# NeoCoreShield2.net
KiCad netlist of a schematic drawn in EAGLE
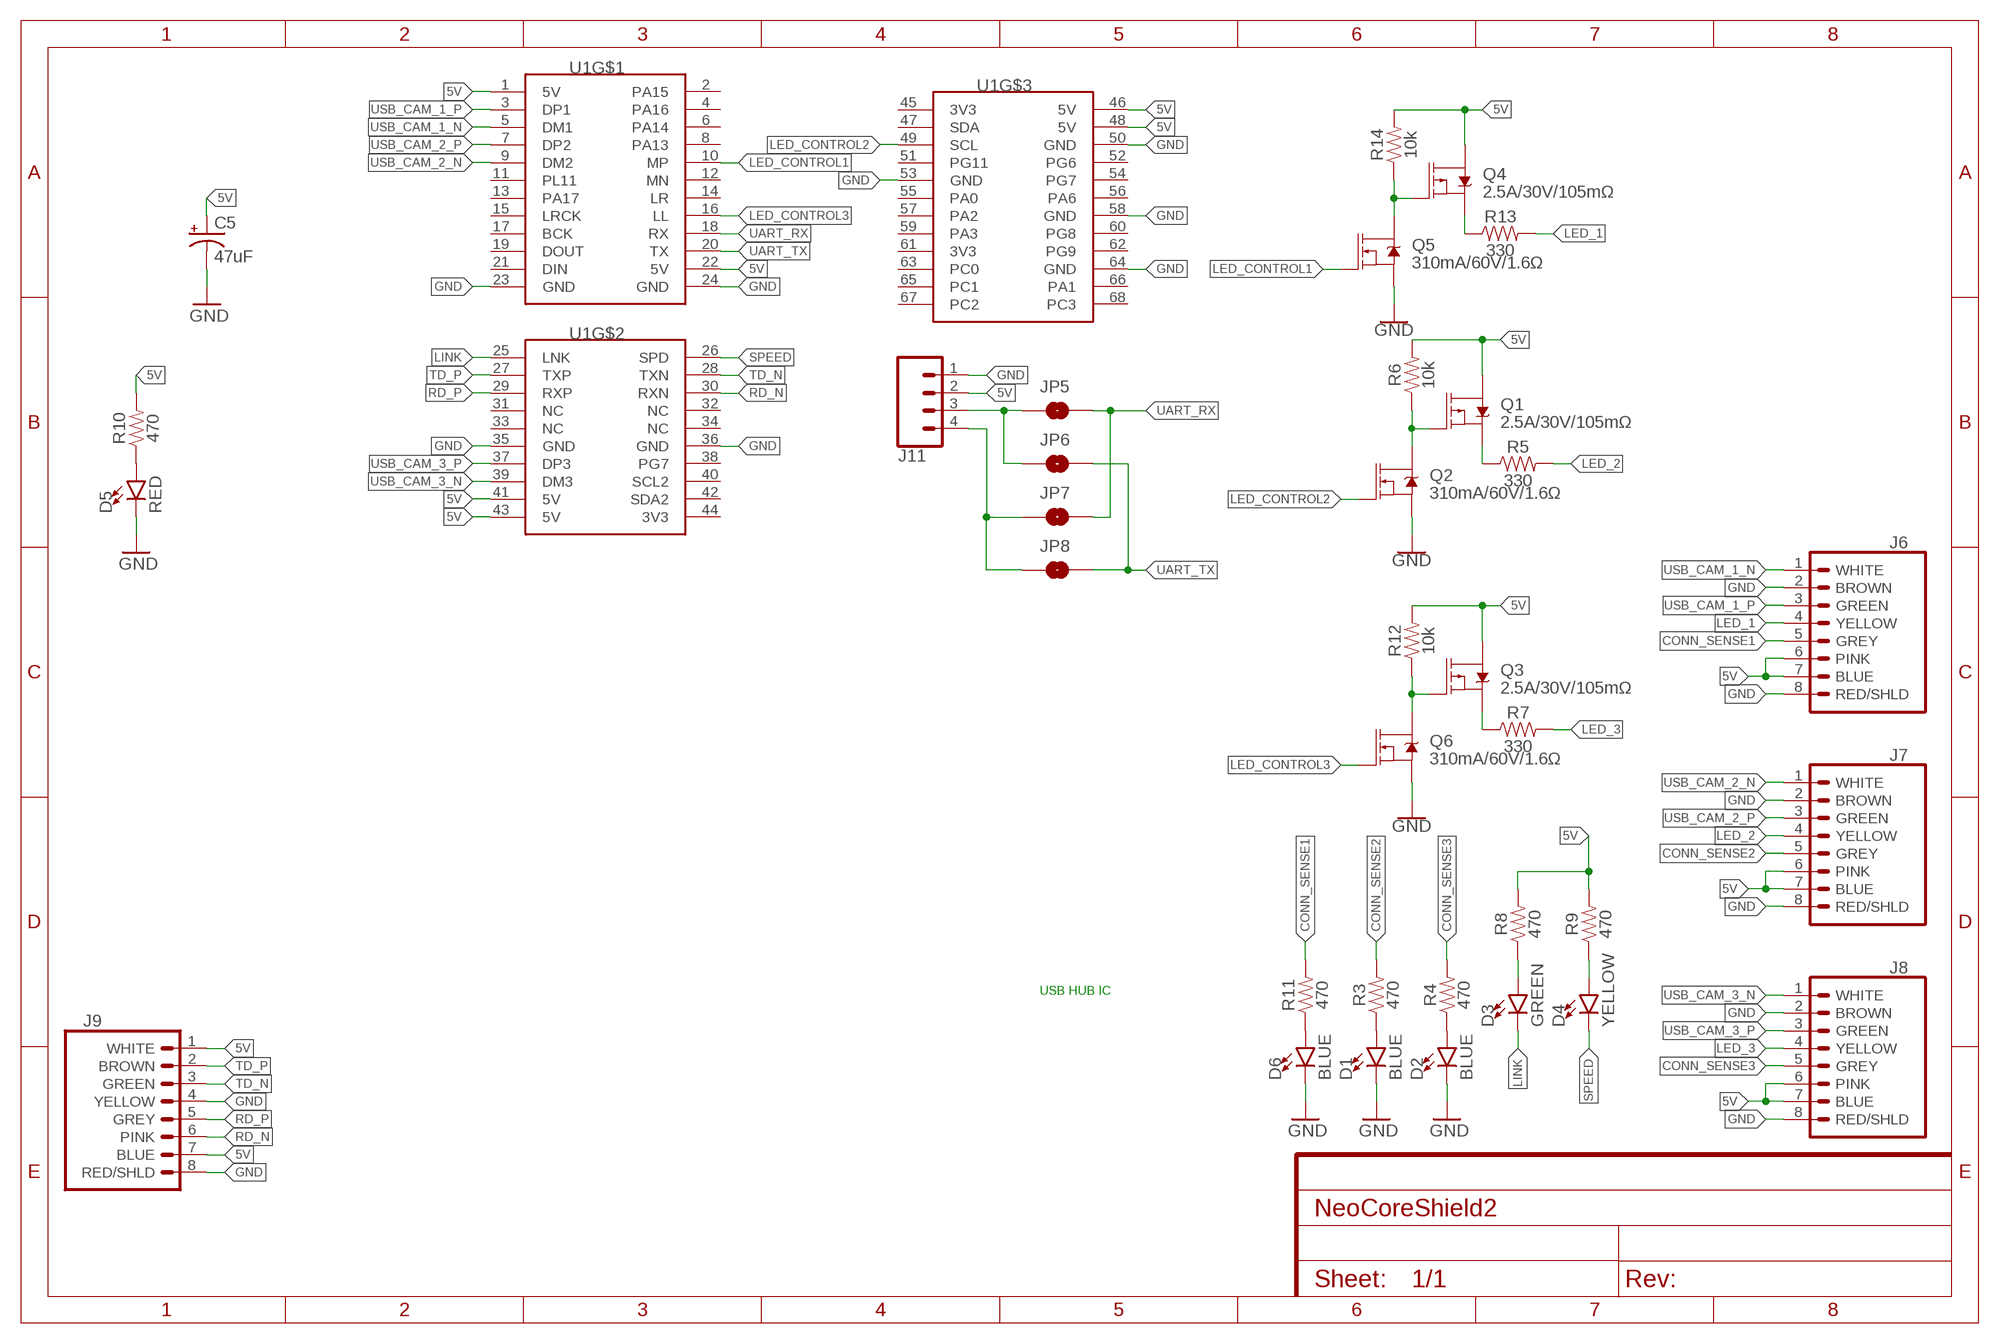
[diagram p0: schematic, sheet 1]

(export (version "E")
  (design (tool "Eeschema 10.0.6"))
  (components
    (comp (ref "C5")
      (value "47uF")
      (footprint "eagle-import:PANASONIC_D")
      (libsource (lib "eagle-import") (part "47UF-POLAR-PANASONIC_D-35V-20%"))
    )
    (comp (ref "D1")
      (value "BLUE")
      (footprint "eagle-import:0805")
      (libsource (lib "eagle-import") (part "LED-0805"))
    )
    (comp (ref "D2")
      (value "BLUE")
      (footprint "eagle-import:0805")
      (libsource (lib "eagle-import") (part "LED-0805"))
    )
    (comp (ref "D3")
      (value "GREEN")
      (footprint "eagle-import:0805")
      (libsource (lib "eagle-import") (part "LED-0805"))
    )
    (comp (ref "D4")
      (value "YELLOW")
      (footprint "eagle-import:0805")
      (libsource (lib "eagle-import") (part "LED-0805"))
    )
    (comp (ref "D5")
      (value "RED")
      (footprint "eagle-import:0805")
      (libsource (lib "eagle-import") (part "LED-0805"))
    )
    (comp (ref "D6")
      (value "BLUE")
      (footprint "eagle-import:0805")
      (libsource (lib "eagle-import") (part "LED-0805"))
    )
    (comp (ref "J6")
      (value "BINDER_M12_PAR_8_DIP")
      (footprint "eagle-import:BINDER_M12_PAR_8_DIP")
      (libsource (lib "eagle-import") (part "BINDER_M12_PAR_8_DIP"))
    )
    (comp (ref "J7")
      (value "BINDER_M12_PAR_8_DIP")
      (footprint "eagle-import:BINDER_M12_PAR_8_DIP")
      (libsource (lib "eagle-import") (part "BINDER_M12_PAR_8_DIP"))
    )
    (comp (ref "J8")
      (value "BINDER_M12_PAR_8_DIP")
      (footprint "eagle-import:BINDER_M12_PAR_8_DIP")
      (libsource (lib "eagle-import") (part "BINDER_M12_PAR_8_DIP"))
    )
    (comp (ref "J9")
      (value "BINDER_M12_PAR_8_DIP")
      (footprint "eagle-import:BINDER_M12_PAR_8_DIP")
      (libsource (lib "eagle-import") (part "BINDER_M12_PAR_8_DIP"))
    )
    (comp (ref "J11")
      (value "CONN_04")
      (footprint "eagle-import:1X04")
      (libsource (lib "eagle-import") (part "CONN_04"))
    )
    (comp (ref "JP5")
      (value "JUMPER-SMT_2_NO_SILK")
      (footprint "eagle-import:SMT-JUMPER_2_NO_SILK")
      (libsource (lib "eagle-import") (part "JUMPER-SMT_2_NO_SILK"))
    )
    (comp (ref "JP6")
      (value "JUMPER-SMT_2_NO_SILK")
      (footprint "eagle-import:SMT-JUMPER_2_NO_SILK")
      (libsource (lib "eagle-import") (part "JUMPER-SMT_2_NO_SILK"))
    )
    (comp (ref "JP7")
      (value "JUMPER-SMT_2_NO_SILK")
      (footprint "eagle-import:SMT-JUMPER_2_NO_SILK")
      (libsource (lib "eagle-import") (part "JUMPER-SMT_2_NO_SILK"))
    )
    (comp (ref "JP8")
      (value "JUMPER-SMT_2_NO_SILK")
      (footprint "eagle-import:SMT-JUMPER_2_NO_SILK")
      (libsource (lib "eagle-import") (part "JUMPER-SMT_2_NO_SILK"))
    )
    (comp (ref "Q1")
      (value "2.5A/30V/105mΩ")
      (footprint "eagle-import:SOT23-3")
      (libsource (lib "eagle-import") (part "MOSFET_PCH-DMG2307L"))
    )
    (comp (ref "Q2")
      (value "310mA/60V/1.6Ω")
      (footprint "eagle-import:SOT323")
      (libsource (lib "eagle-import") (part "MOSFET-NCH-2N7002PW"))
    )
    (comp (ref "Q3")
      (value "2.5A/30V/105mΩ")
      (footprint "eagle-import:SOT23-3")
      (libsource (lib "eagle-import") (part "MOSFET_PCH-DMG2307L"))
    )
    (comp (ref "Q4")
      (value "2.5A/30V/105mΩ")
      (footprint "eagle-import:SOT23-3")
      (libsource (lib "eagle-import") (part "MOSFET_PCH-DMG2307L"))
    )
    (comp (ref "Q5")
      (value "310mA/60V/1.6Ω")
      (footprint "eagle-import:SOT323")
      (libsource (lib "eagle-import") (part "MOSFET-NCH-2N7002PW"))
    )
    (comp (ref "Q6")
      (value "310mA/60V/1.6Ω")
      (footprint "eagle-import:SOT323")
      (libsource (lib "eagle-import") (part "MOSFET-NCH-2N7002PW"))
    )
    (comp (ref "R3")
      (value "470")
      (footprint "eagle-import:0603")
      (libsource (lib "eagle-import") (part "0OHM-0603-1/10W-5%"))
    )
    (comp (ref "R4")
      (value "470")
      (footprint "eagle-import:0603")
      (libsource (lib "eagle-import") (part "0OHM-0603-1/10W-5%"))
    )
    (comp (ref "R5")
      (value "330")
      (footprint "eagle-import:0805")
      (libsource (lib "eagle-import") (part "RESISTOR0805"))
    )
    (comp (ref "R6")
      (value "10k")
      (footprint "eagle-import:0603")
      (libsource (lib "eagle-import") (part "10KOHM-0603-1/10W-1%"))
    )
    (comp (ref "R7")
      (value "330")
      (footprint "eagle-import:0805")
      (libsource (lib "eagle-import") (part "RESISTOR0805"))
    )
    (comp (ref "R8")
      (value "470")
      (footprint "eagle-import:0603")
      (libsource (lib "eagle-import") (part "0OHM-0603-1/10W-5%"))
    )
    (comp (ref "R9")
      (value "470")
      (footprint "eagle-import:0603")
      (libsource (lib "eagle-import") (part "0OHM-0603-1/10W-5%"))
    )
    (comp (ref "R10")
      (value "470")
      (footprint "eagle-import:0603")
      (libsource (lib "eagle-import") (part "0OHM-0603-1/10W-5%"))
    )
    (comp (ref "R11")
      (value "470")
      (footprint "eagle-import:0603")
      (libsource (lib "eagle-import") (part "0OHM-0603-1/10W-5%"))
    )
    (comp (ref "R12")
      (value "10k")
      (footprint "eagle-import:0603")
      (libsource (lib "eagle-import") (part "10KOHM-0603-1/10W-1%"))
    )
    (comp (ref "R13")
      (value "330")
      (footprint "eagle-import:0805")
      (libsource (lib "eagle-import") (part "RESISTOR0805"))
    )
    (comp (ref "R14")
      (value "10k")
      (footprint "eagle-import:0603")
      (libsource (lib "eagle-import") (part "10KOHM-0603-1/10W-1%"))
    )
    (comp (ref "U1")
      (value "NANO_PI_NEO_CORE")
      (footprint "eagle-import:NANO_PI_NEO_CORE")
      (libsource (lib "eagle-import") (part "NANO_PI_NEO_CORE"))
    )
  )
  (nets
    (net (code "1") (name "5V") (class "Default")
      (node (ref "C5") (pin "+") (pinfunction "+_+") (pintype "passive"))
      (node (ref "J11") (pin "2") (pinfunction "2_2") (pintype "passive"))
      (node (ref "J6") (pin "6") (pinfunction "PINK_6") (pintype "passive"))
      (node (ref "J6") (pin "7") (pinfunction "BLUE_7") (pintype "passive"))
      (node (ref "J7") (pin "6") (pinfunction "PINK_6") (pintype "passive"))
      (node (ref "J7") (pin "7") (pinfunction "BLUE_7") (pintype "passive"))
      (node (ref "J8") (pin "6") (pinfunction "PINK_6") (pintype "passive"))
      (node (ref "J8") (pin "7") (pinfunction "BLUE_7") (pintype "passive"))
      (node (ref "J9") (pin "1") (pinfunction "WHITE_1") (pintype "passive"))
      (node (ref "J9") (pin "7") (pinfunction "BLUE_7") (pintype "passive"))
      (node (ref "Q1") (pin "3") (pinfunction "D_3") (pintype "bidirectional"))
      (node (ref "Q3") (pin "3") (pinfunction "D_3") (pintype "bidirectional"))
      (node (ref "Q4") (pin "3") (pinfunction "D_3") (pintype "bidirectional"))
      (node (ref "R10") (pin "2") (pinfunction "2_2") (pintype "passive"))
      (node (ref "R12") (pin "2") (pinfunction "2_2") (pintype "passive"))
      (node (ref "R14") (pin "2") (pinfunction "2_2") (pintype "passive"))
      (node (ref "R6") (pin "2") (pinfunction "2_2") (pintype "passive"))
      (node (ref "R8") (pin "2") (pinfunction "2_2") (pintype "passive"))
      (node (ref "R9") (pin "2") (pinfunction "2_2") (pintype "passive"))
      (node (ref "U1") (pin "1") (pinfunction "5V_1") (pintype "bidirectional"))
      (node (ref "U1") (pin "22") (pinfunction "5V_22") (pintype "bidirectional"))
      (node (ref "U1") (pin "41") (pinfunction "5V_41") (pintype "bidirectional"))
      (node (ref "U1") (pin "43") (pinfunction "5V_43") (pintype "bidirectional"))
      (node (ref "U1") (pin "46") (pinfunction "5V_46") (pintype "bidirectional"))
      (node (ref "U1") (pin "48") (pinfunction "5V_48") (pintype "bidirectional"))
    )
    (net (code "2") (name "CONN_SENSE1") (class "Default")
      (node (ref "J6") (pin "5") (pinfunction "GREY_5") (pintype "passive"))
      (node (ref "R11") (pin "2") (pinfunction "2_2") (pintype "passive"))
    )
    (net (code "3") (name "CONN_SENSE2") (class "Default")
      (node (ref "J7") (pin "5") (pinfunction "GREY_5") (pintype "passive"))
      (node (ref "R3") (pin "2") (pinfunction "2_2") (pintype "passive"))
    )
    (net (code "4") (name "CONN_SENSE3") (class "Default")
      (node (ref "J8") (pin "5") (pinfunction "GREY_5") (pintype "passive"))
      (node (ref "R4") (pin "2") (pinfunction "2_2") (pintype "passive"))
    )
    (net (code "5") (name "GND") (class "Default")
      (node (ref "C5") (pin "-") (pinfunction "-_-") (pintype "passive"))
      (node (ref "D1") (pin "C") (pinfunction "C_C") (pintype "passive"))
      (node (ref "D2") (pin "C") (pinfunction "C_C") (pintype "passive"))
      (node (ref "D5") (pin "C") (pinfunction "C_C") (pintype "passive"))
      (node (ref "D6") (pin "C") (pinfunction "C_C") (pintype "passive"))
      (node (ref "J11") (pin "1") (pinfunction "1_1") (pintype "passive"))
      (node (ref "J6") (pin "2") (pinfunction "BROWN_2") (pintype "passive"))
      (node (ref "J6") (pin "8") (pinfunction "RED/SHLD_8") (pintype "passive"))
      (node (ref "J7") (pin "2") (pinfunction "BROWN_2") (pintype "passive"))
      (node (ref "J7") (pin "8") (pinfunction "RED/SHLD_8") (pintype "passive"))
      (node (ref "J8") (pin "2") (pinfunction "BROWN_2") (pintype "passive"))
      (node (ref "J8") (pin "8") (pinfunction "RED/SHLD_8") (pintype "passive"))
      (node (ref "J9") (pin "4") (pinfunction "YELLOW_4") (pintype "passive"))
      (node (ref "J9") (pin "8") (pinfunction "RED/SHLD_8") (pintype "passive"))
      (node (ref "Q2") (pin "2") (pinfunction "S_2") (pintype "bidirectional"))
      (node (ref "Q5") (pin "2") (pinfunction "S_2") (pintype "bidirectional"))
      (node (ref "Q6") (pin "2") (pinfunction "S_2") (pintype "bidirectional"))
      (node (ref "U1") (pin "23") (pinfunction "GND_23") (pintype "bidirectional"))
      (node (ref "U1") (pin "24") (pinfunction "GND_24") (pintype "bidirectional"))
      (node (ref "U1") (pin "35") (pinfunction "GND_35") (pintype "bidirectional"))
      (node (ref "U1") (pin "36") (pinfunction "GND_36") (pintype "bidirectional"))
      (node (ref "U1") (pin "50") (pinfunction "GND_50") (pintype "bidirectional"))
      (node (ref "U1") (pin "53") (pinfunction "GND_53") (pintype "bidirectional"))
      (node (ref "U1") (pin "58") (pinfunction "GND_58") (pintype "bidirectional"))
      (node (ref "U1") (pin "64") (pinfunction "GND_64") (pintype "bidirectional"))
    )
    (net (code "6") (name "LED_1") (class "Default")
      (node (ref "J6") (pin "4") (pinfunction "YELLOW_4") (pintype "passive"))
      (node (ref "R13") (pin "2") (pinfunction "2_2") (pintype "passive"))
    )
    (net (code "7") (name "LED_2") (class "Default")
      (node (ref "J7") (pin "4") (pinfunction "YELLOW_4") (pintype "passive"))
      (node (ref "R5") (pin "2") (pinfunction "2_2") (pintype "passive"))
    )
    (net (code "8") (name "LED_3") (class "Default")
      (node (ref "J8") (pin "4") (pinfunction "YELLOW_4") (pintype "passive"))
      (node (ref "R7") (pin "2") (pinfunction "2_2") (pintype "passive"))
    )
    (net (code "9") (name "LED_CONTROL1") (class "Default")
      (node (ref "Q5") (pin "1") (pinfunction "G_1") (pintype "bidirectional"))
      (node (ref "U1") (pin "10") (pinfunction "MP_10") (pintype "bidirectional"))
    )
    (net (code "10") (name "LED_CONTROL2") (class "Default")
      (node (ref "Q2") (pin "1") (pinfunction "G_1") (pintype "bidirectional"))
      (node (ref "U1") (pin "49") (pinfunction "SCL_49") (pintype "bidirectional"))
    )
    (net (code "11") (name "LED_CONTROL3") (class "Default")
      (node (ref "Q6") (pin "1") (pinfunction "G_1") (pintype "bidirectional"))
      (node (ref "U1") (pin "16") (pinfunction "LL_16") (pintype "bidirectional"))
    )
    (net (code "12") (name "LINK") (class "Default")
      (node (ref "D3") (pin "C") (pinfunction "C_C") (pintype "passive"))
      (node (ref "U1") (pin "25") (pinfunction "LNK_25") (pintype "bidirectional"))
    )
    (net (code "13") (name "Net-(D1-PadA)") (class "Default")
      (node (ref "D1") (pin "A") (pinfunction "A_A") (pintype "passive"))
      (node (ref "R3") (pin "1") (pinfunction "1_1") (pintype "passive"))
    )
    (net (code "14") (name "Net-(D2-PadA)") (class "Default")
      (node (ref "D2") (pin "A") (pinfunction "A_A") (pintype "passive"))
      (node (ref "R4") (pin "1") (pinfunction "1_1") (pintype "passive"))
    )
    (net (code "15") (name "Net-(D3-PadA)") (class "Default")
      (node (ref "D3") (pin "A") (pinfunction "A_A") (pintype "passive"))
      (node (ref "R8") (pin "1") (pinfunction "1_1") (pintype "passive"))
    )
    (net (code "16") (name "Net-(D4-PadA)") (class "Default")
      (node (ref "D4") (pin "A") (pinfunction "A_A") (pintype "passive"))
      (node (ref "R9") (pin "1") (pinfunction "1_1") (pintype "passive"))
    )
    (net (code "17") (name "Net-(D5-PadA)") (class "Default")
      (node (ref "D5") (pin "A") (pinfunction "A_A") (pintype "passive"))
      (node (ref "R10") (pin "1") (pinfunction "1_1") (pintype "passive"))
    )
    (net (code "18") (name "Net-(D6-PadA)") (class "Default")
      (node (ref "D6") (pin "A") (pinfunction "A_A") (pintype "passive"))
      (node (ref "R11") (pin "1") (pinfunction "1_1") (pintype "passive"))
    )
    (net (code "19") (name "Net-(J11-Pad3)") (class "Default")
      (node (ref "J11") (pin "3") (pinfunction "3_3") (pintype "passive"))
      (node (ref "JP5") (pin "1") (pinfunction "1_1") (pintype "passive"))
      (node (ref "JP6") (pin "1") (pinfunction "1_1") (pintype "passive"))
    )
    (net (code "20") (name "Net-(J11-Pad4)") (class "Default")
      (node (ref "J11") (pin "4") (pinfunction "4_4") (pintype "passive"))
      (node (ref "JP7") (pin "1") (pinfunction "1_1") (pintype "passive"))
      (node (ref "JP8") (pin "1") (pinfunction "1_1") (pintype "passive"))
    )
    (net (code "21") (name "Net-(Q1-G)") (class "Default")
      (node (ref "Q1") (pin "1") (pinfunction "G_1") (pintype "bidirectional"))
      (node (ref "Q2") (pin "3") (pinfunction "D_3") (pintype "bidirectional"))
      (node (ref "R6") (pin "1") (pinfunction "1_1") (pintype "passive"))
    )
    (net (code "22") (name "Net-(Q1-S)") (class "Default")
      (node (ref "Q1") (pin "2") (pinfunction "S_2") (pintype "bidirectional"))
      (node (ref "R5") (pin "1") (pinfunction "1_1") (pintype "passive"))
    )
    (net (code "23") (name "Net-(Q3-G)") (class "Default")
      (node (ref "Q3") (pin "1") (pinfunction "G_1") (pintype "bidirectional"))
      (node (ref "Q6") (pin "3") (pinfunction "D_3") (pintype "bidirectional"))
      (node (ref "R12") (pin "1") (pinfunction "1_1") (pintype "passive"))
    )
    (net (code "24") (name "Net-(Q3-S)") (class "Default")
      (node (ref "Q3") (pin "2") (pinfunction "S_2") (pintype "bidirectional"))
      (node (ref "R7") (pin "1") (pinfunction "1_1") (pintype "passive"))
    )
    (net (code "25") (name "Net-(Q4-G)") (class "Default")
      (node (ref "Q4") (pin "1") (pinfunction "G_1") (pintype "bidirectional"))
      (node (ref "Q5") (pin "3") (pinfunction "D_3") (pintype "bidirectional"))
      (node (ref "R14") (pin "1") (pinfunction "1_1") (pintype "passive"))
    )
    (net (code "26") (name "Net-(Q4-S)") (class "Default")
      (node (ref "Q4") (pin "2") (pinfunction "S_2") (pintype "bidirectional"))
      (node (ref "R13") (pin "1") (pinfunction "1_1") (pintype "passive"))
    )
    (net (code "27") (name "RD_N") (class "Default")
      (node (ref "J9") (pin "6") (pinfunction "PINK_6") (pintype "passive"))
      (node (ref "U1") (pin "30") (pinfunction "RXN_30") (pintype "bidirectional"))
    )
    (net (code "28") (name "RD_P") (class "Default")
      (node (ref "J9") (pin "5") (pinfunction "GREY_5") (pintype "passive"))
      (node (ref "U1") (pin "29") (pinfunction "RXP_29") (pintype "bidirectional"))
    )
    (net (code "29") (name "SPEED") (class "Default")
      (node (ref "D4") (pin "C") (pinfunction "C_C") (pintype "passive"))
      (node (ref "U1") (pin "26") (pinfunction "SPD_26") (pintype "bidirectional"))
    )
    (net (code "30") (name "TD_N") (class "Default")
      (node (ref "J9") (pin "3") (pinfunction "GREEN_3") (pintype "passive"))
      (node (ref "U1") (pin "28") (pinfunction "TXN_28") (pintype "bidirectional"))
    )
    (net (code "31") (name "TD_P") (class "Default")
      (node (ref "J9") (pin "2") (pinfunction "BROWN_2") (pintype "passive"))
      (node (ref "U1") (pin "27") (pinfunction "TXP_27") (pintype "bidirectional"))
    )
    (net (code "32") (name "UART_RX") (class "Default")
      (node (ref "JP5") (pin "2") (pinfunction "2_2") (pintype "passive"))
      (node (ref "JP7") (pin "2") (pinfunction "2_2") (pintype "passive"))
      (node (ref "U1") (pin "18") (pinfunction "RX_18") (pintype "bidirectional"))
    )
    (net (code "33") (name "UART_TX") (class "Default")
      (node (ref "JP6") (pin "2") (pinfunction "2_2") (pintype "passive"))
      (node (ref "JP8") (pin "2") (pinfunction "2_2") (pintype "passive"))
      (node (ref "U1") (pin "20") (pinfunction "TX_20") (pintype "bidirectional"))
    )
    (net (code "34") (name "USB_CAM_1_N") (class "Default")
      (node (ref "J6") (pin "1") (pinfunction "WHITE_1") (pintype "passive"))
      (node (ref "U1") (pin "5") (pinfunction "DM1_5") (pintype "bidirectional"))
    )
    (net (code "35") (name "USB_CAM_1_P") (class "Default")
      (node (ref "J6") (pin "3") (pinfunction "GREEN_3") (pintype "passive"))
      (node (ref "U1") (pin "3") (pinfunction "DP1_3") (pintype "bidirectional"))
    )
    (net (code "36") (name "USB_CAM_2_N") (class "Default")
      (node (ref "J7") (pin "1") (pinfunction "WHITE_1") (pintype "passive"))
      (node (ref "U1") (pin "9") (pinfunction "DM2_9") (pintype "bidirectional"))
    )
    (net (code "37") (name "USB_CAM_2_P") (class "Default")
      (node (ref "J7") (pin "3") (pinfunction "GREEN_3") (pintype "passive"))
      (node (ref "U1") (pin "7") (pinfunction "DP2_7") (pintype "bidirectional"))
    )
    (net (code "38") (name "USB_CAM_3_N") (class "Default")
      (node (ref "J8") (pin "1") (pinfunction "WHITE_1") (pintype "passive"))
      (node (ref "U1") (pin "39") (pinfunction "DM3_39") (pintype "bidirectional"))
    )
    (net (code "39") (name "USB_CAM_3_P") (class "Default")
      (node (ref "J8") (pin "3") (pinfunction "GREEN_3") (pintype "passive"))
      (node (ref "U1") (pin "37") (pinfunction "DP3_37") (pintype "bidirectional"))
    )
    (net (code "40") (name "unconnected-(U1A-BCK-Pad17)") (class "Default")
      (node (ref "U1") (pin "17") (pinfunction "BCK_17") (pintype "bidirectional"))
    )
    (net (code "41") (name "unconnected-(U1A-DIN-Pad21)") (class "Default")
      (node (ref "U1") (pin "21") (pinfunction "DIN_21") (pintype "bidirectional"))
    )
    (net (code "42") (name "unconnected-(U1A-DOUT-Pad19)") (class "Default")
      (node (ref "U1") (pin "19") (pinfunction "DOUT_19") (pintype "bidirectional"))
    )
    (net (code "43") (name "unconnected-(U1A-LR-Pad14)") (class "Default")
      (node (ref "U1") (pin "14") (pinfunction "LR_14") (pintype "bidirectional"))
    )
    (net (code "44") (name "unconnected-(U1A-LRCK-Pad15)") (class "Default")
      (node (ref "U1") (pin "15") (pinfunction "LRCK_15") (pintype "bidirectional"))
    )
    (net (code "45") (name "unconnected-(U1A-MN-Pad12)") (class "Default")
      (node (ref "U1") (pin "12") (pinfunction "MN_12") (pintype "bidirectional"))
    )
    (net (code "46") (name "unconnected-(U1A-PA13-Pad8)") (class "Default")
      (node (ref "U1") (pin "8") (pinfunction "PA13_8") (pintype "bidirectional"))
    )
    (net (code "47") (name "unconnected-(U1A-PA14-Pad6)") (class "Default")
      (node (ref "U1") (pin "6") (pinfunction "PA14_6") (pintype "bidirectional"))
    )
    (net (code "48") (name "unconnected-(U1A-PA15-Pad2)") (class "Default")
      (node (ref "U1") (pin "2") (pinfunction "PA15_2") (pintype "bidirectional"))
    )
    (net (code "49") (name "unconnected-(U1A-PA16-Pad4)") (class "Default")
      (node (ref "U1") (pin "4") (pinfunction "PA16_4") (pintype "bidirectional"))
    )
    (net (code "50") (name "unconnected-(U1A-PA17-Pad13)") (class "Default")
      (node (ref "U1") (pin "13") (pinfunction "PA17_13") (pintype "bidirectional"))
    )
    (net (code "51") (name "unconnected-(U1A-PL11-Pad11)") (class "Default")
      (node (ref "U1") (pin "11") (pinfunction "PL11_11") (pintype "bidirectional"))
    )
    (net (code "52") (name "unconnected-(U1B-3V3-Pad44)") (class "Default")
      (node (ref "U1") (pin "44") (pinfunction "3V3_44") (pintype "bidirectional"))
    )
    (net (code "53") (name "unconnected-(U1B-NC-Pad31)") (class "Default")
      (node (ref "U1") (pin "31") (pinfunction "NC_31") (pintype "bidirectional"))
    )
    (net (code "54") (name "unconnected-(U1B-NC-Pad32)") (class "Default")
      (node (ref "U1") (pin "32") (pinfunction "NC_32") (pintype "bidirectional"))
    )
    (net (code "55") (name "unconnected-(U1B-NC-Pad33)") (class "Default")
      (node (ref "U1") (pin "33") (pinfunction "NC_33") (pintype "bidirectional"))
    )
    (net (code "56") (name "unconnected-(U1B-NC-Pad34)") (class "Default")
      (node (ref "U1") (pin "34") (pinfunction "NC_34") (pintype "bidirectional"))
    )
    (net (code "57") (name "unconnected-(U1B-PG7-Pad38)") (class "Default")
      (node (ref "U1") (pin "38") (pinfunction "PG7_38") (pintype "bidirectional"))
    )
    (net (code "58") (name "unconnected-(U1B-SCL2-Pad40)") (class "Default")
      (node (ref "U1") (pin "40") (pinfunction "SCL2_40") (pintype "bidirectional"))
    )
    (net (code "59") (name "unconnected-(U1B-SDA2-Pad42)") (class "Default")
      (node (ref "U1") (pin "42") (pinfunction "SDA2_42") (pintype "bidirectional"))
    )
    (net (code "60") (name "unconnected-(U1C-3V3-Pad45)") (class "Default")
      (node (ref "U1") (pin "45") (pinfunction "3V3_45") (pintype "bidirectional"))
    )
    (net (code "61") (name "unconnected-(U1C-3V3-Pad61)") (class "Default")
      (node (ref "U1") (pin "61") (pinfunction "3V3_61") (pintype "bidirectional"))
    )
    (net (code "62") (name "unconnected-(U1C-PA0-Pad55)") (class "Default")
      (node (ref "U1") (pin "55") (pinfunction "PA0_55") (pintype "bidirectional"))
    )
    (net (code "63") (name "unconnected-(U1C-PA1-Pad66)") (class "Default")
      (node (ref "U1") (pin "66") (pinfunction "PA1_66") (pintype "bidirectional"))
    )
    (net (code "64") (name "unconnected-(U1C-PA2-Pad57)") (class "Default")
      (node (ref "U1") (pin "57") (pinfunction "PA2_57") (pintype "bidirectional"))
    )
    (net (code "65") (name "unconnected-(U1C-PA3-Pad59)") (class "Default")
      (node (ref "U1") (pin "59") (pinfunction "PA3_59") (pintype "bidirectional"))
    )
    (net (code "66") (name "unconnected-(U1C-PA6-Pad56)") (class "Default")
      (node (ref "U1") (pin "56") (pinfunction "PA6_56") (pintype "bidirectional"))
    )
    (net (code "67") (name "unconnected-(U1C-PC0-Pad63)") (class "Default")
      (node (ref "U1") (pin "63") (pinfunction "PC0_63") (pintype "bidirectional"))
    )
    (net (code "68") (name "unconnected-(U1C-PC1-Pad65)") (class "Default")
      (node (ref "U1") (pin "65") (pinfunction "PC1_65") (pintype "bidirectional"))
    )
    (net (code "69") (name "unconnected-(U1C-PC2-Pad67)") (class "Default")
      (node (ref "U1") (pin "67") (pinfunction "PC2_67") (pintype "bidirectional"))
    )
    (net (code "70") (name "unconnected-(U1C-PC3-Pad68)") (class "Default")
      (node (ref "U1") (pin "68") (pinfunction "PC3_68") (pintype "bidirectional"))
    )
    (net (code "71") (name "unconnected-(U1C-PG6-Pad52)") (class "Default")
      (node (ref "U1") (pin "52") (pinfunction "PG6_52") (pintype "bidirectional"))
    )
    (net (code "72") (name "unconnected-(U1C-PG7-Pad54)") (class "Default")
      (node (ref "U1") (pin "54") (pinfunction "PG7_54") (pintype "bidirectional"))
    )
    (net (code "73") (name "unconnected-(U1C-PG8-Pad60)") (class "Default")
      (node (ref "U1") (pin "60") (pinfunction "PG8_60") (pintype "bidirectional"))
    )
    (net (code "74") (name "unconnected-(U1C-PG9-Pad62)") (class "Default")
      (node (ref "U1") (pin "62") (pinfunction "PG9_62") (pintype "bidirectional"))
    )
    (net (code "75") (name "unconnected-(U1C-PG11-Pad51)") (class "Default")
      (node (ref "U1") (pin "51") (pinfunction "PG11_51") (pintype "bidirectional"))
    )
    (net (code "76") (name "unconnected-(U1C-SDA-Pad47)") (class "Default")
      (node (ref "U1") (pin "47") (pinfunction "SDA_47") (pintype "bidirectional"))
    )
  )
)
